# filter-8.net
KiCad netlist of a schematic drawn in Altium Designer
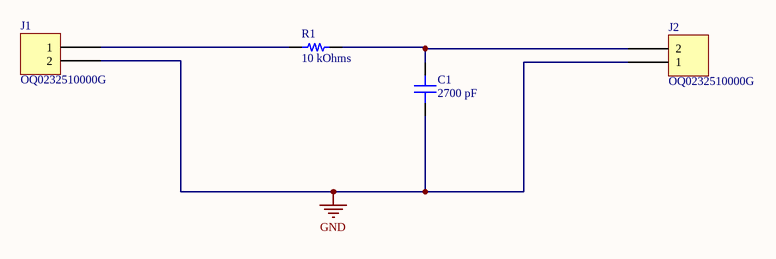
[diagram p0: filter-8.SchDoc]

(export (version "E")
  (design (tool "Eeschema 10.0.6"))
  (components
    (comp (ref "C1")
      (value "2700 pF")
      (footprint "CAP 0603_1608")
      (description "CAP CER 2700PF 25V NP0 0603")
      (fields (field (name "PART NUMBER") "C0603C272F3GAC7867") (field (name "MANUFACTURER") "KEMET"))
      (libsource (lib "Celestial Altium Library - altium_library") (part "Capacitor"))
    )
    (comp (ref "J1")
      (value "OQ0232510000G")
      (footprint "FCI 06-381-2PIN")
      (description "TERM BLOCK HDR 2POS 90DEG 3.81MM")
      (fields (field (name "MANUFACTURER") "Amphenol Anytek"))
      (libsource (lib "Celestial Altium Library - altium_library") (part "2 Pin"))
    )
    (comp (ref "J2")
      (value "OQ0232510000G")
      (footprint "FCI 06-381-2PIN")
      (description "TERM BLOCK HDR 2POS 90DEG 3.81MM")
      (fields (field (name "MANUFACTURER") "Amphenol Anytek"))
      (libsource (lib "") (part "2 Pin_1"))
    )
    (comp (ref "R1")
      (value "10 kOhms")
      (footprint "RES 0603_1608")
      (description "RES 10K OHM 0.1% 1/16W 0603")
      (fields
        (field (name "PART NUMBER") "RNCS0603BKE10K0")
        (field (name "MANUFACTURER") "Stackpole Electronics Inc")
      )
      (libsource (lib "Celestial Altium Library - altium_library") (part "Resistor"))
    )
  )
  (nets
    (net (code "1") (name "GND") (class "Default")
      (node (ref "C1") (pin "1") (pinfunction "1_1") (pintype "passive"))
      (node (ref "J1") (pin "2") (pinfunction "2_2") (pintype "passive"))
      (node (ref "J2") (pin "1") (pinfunction "1_1") (pintype "passive"))
    )
    (net (code "2") (name "Net-(C1-Pad2)") (class "Default")
      (node (ref "C1") (pin "2") (pinfunction "2_2") (pintype "passive"))
      (node (ref "J2") (pin "2") (pinfunction "2_2") (pintype "passive"))
      (node (ref "R1") (pin "2") (pinfunction "2_2") (pintype "passive"))
    )
    (net (code "3") (name "Net-(J1-Pad1)") (class "Default")
      (node (ref "J1") (pin "1") (pinfunction "1_1") (pintype "passive"))
      (node (ref "R1") (pin "1") (pinfunction "1_1") (pintype "passive"))
    )
  )
)
